# EEZ_DIB_AUX_PS_r1B1.net
KiCad netlist of a schematic drawn in EAGLE
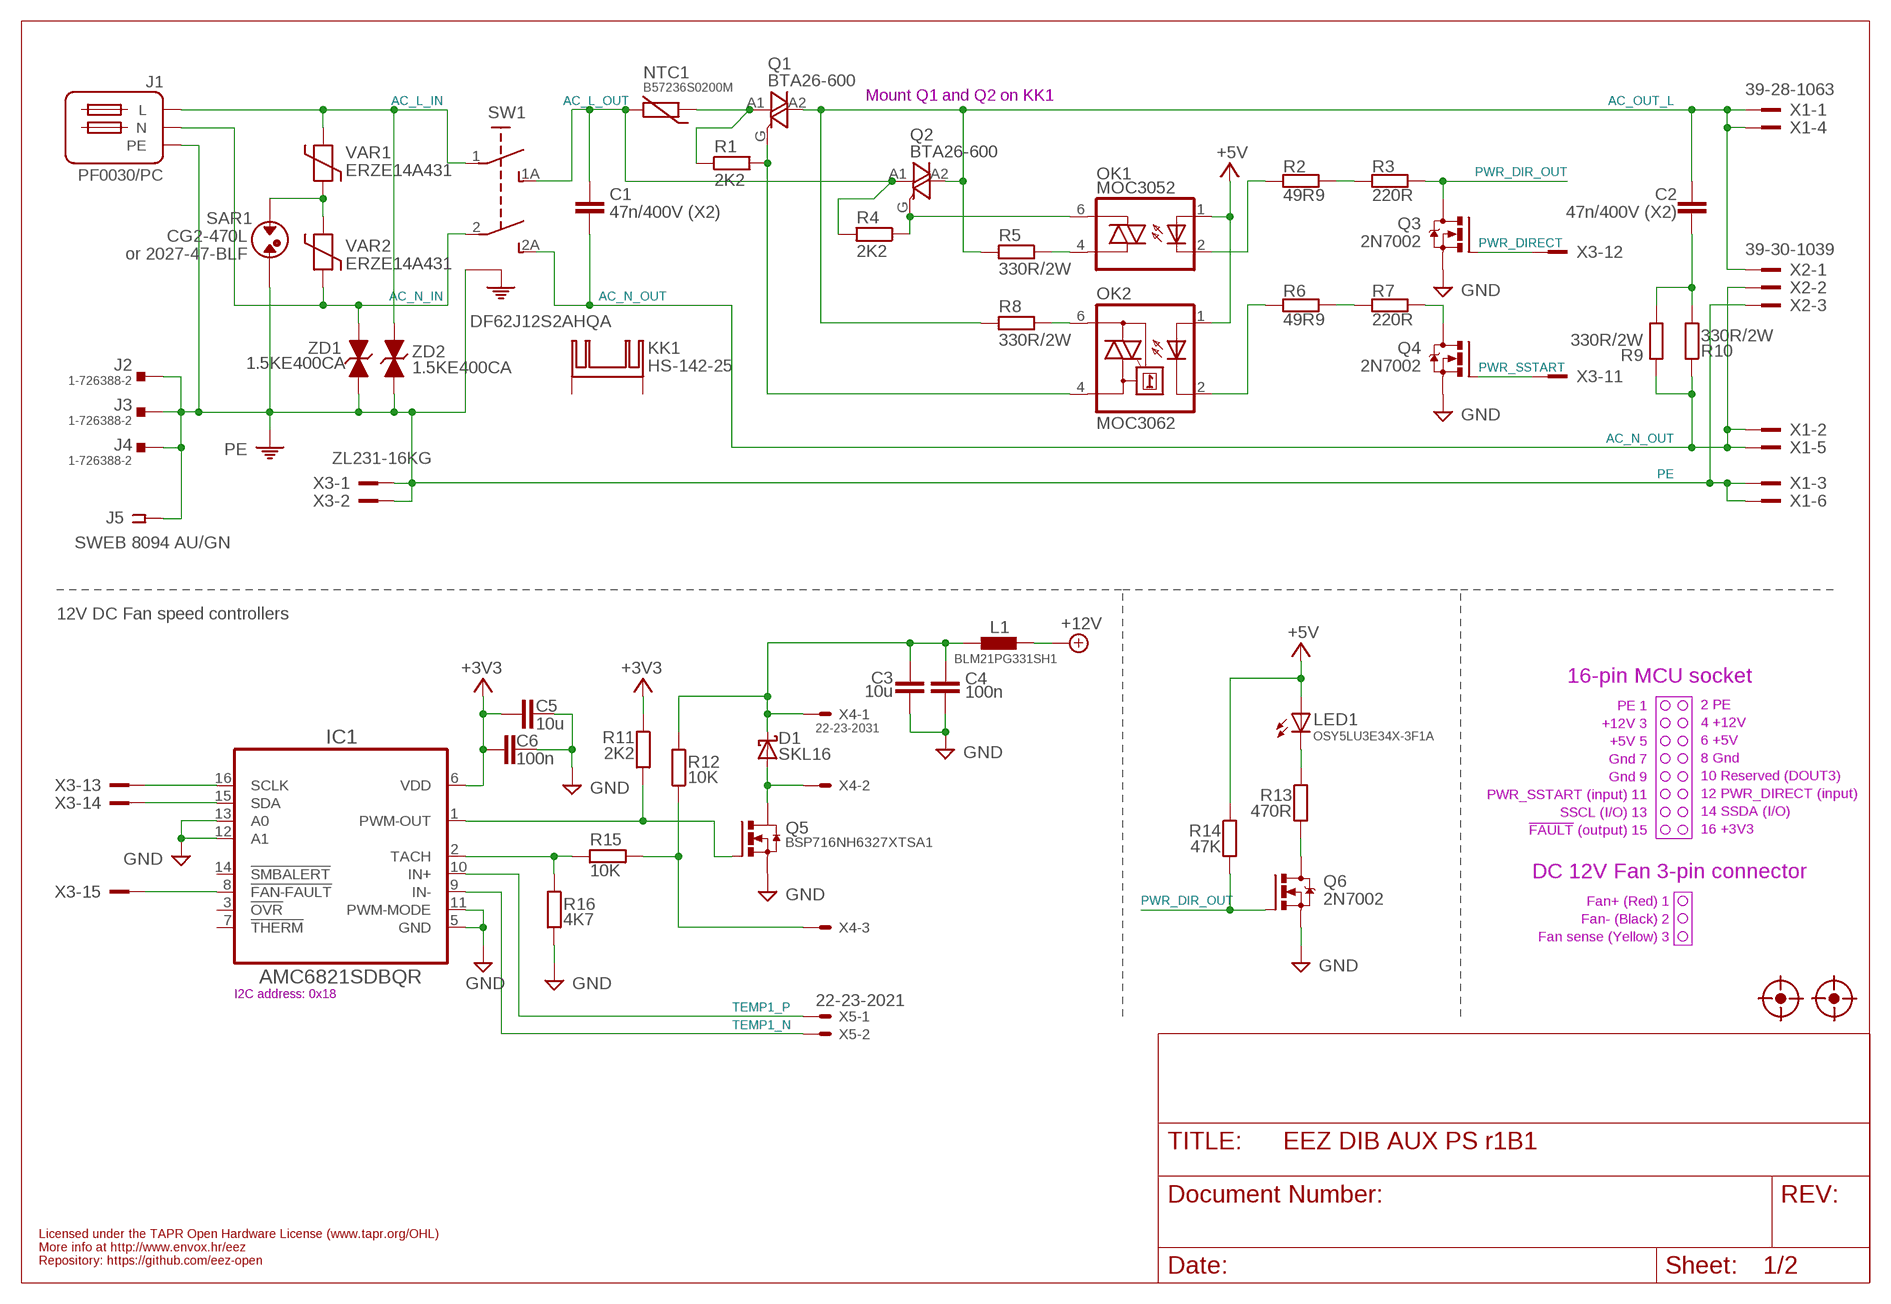
[diagram p0: schematic, sheet 1]
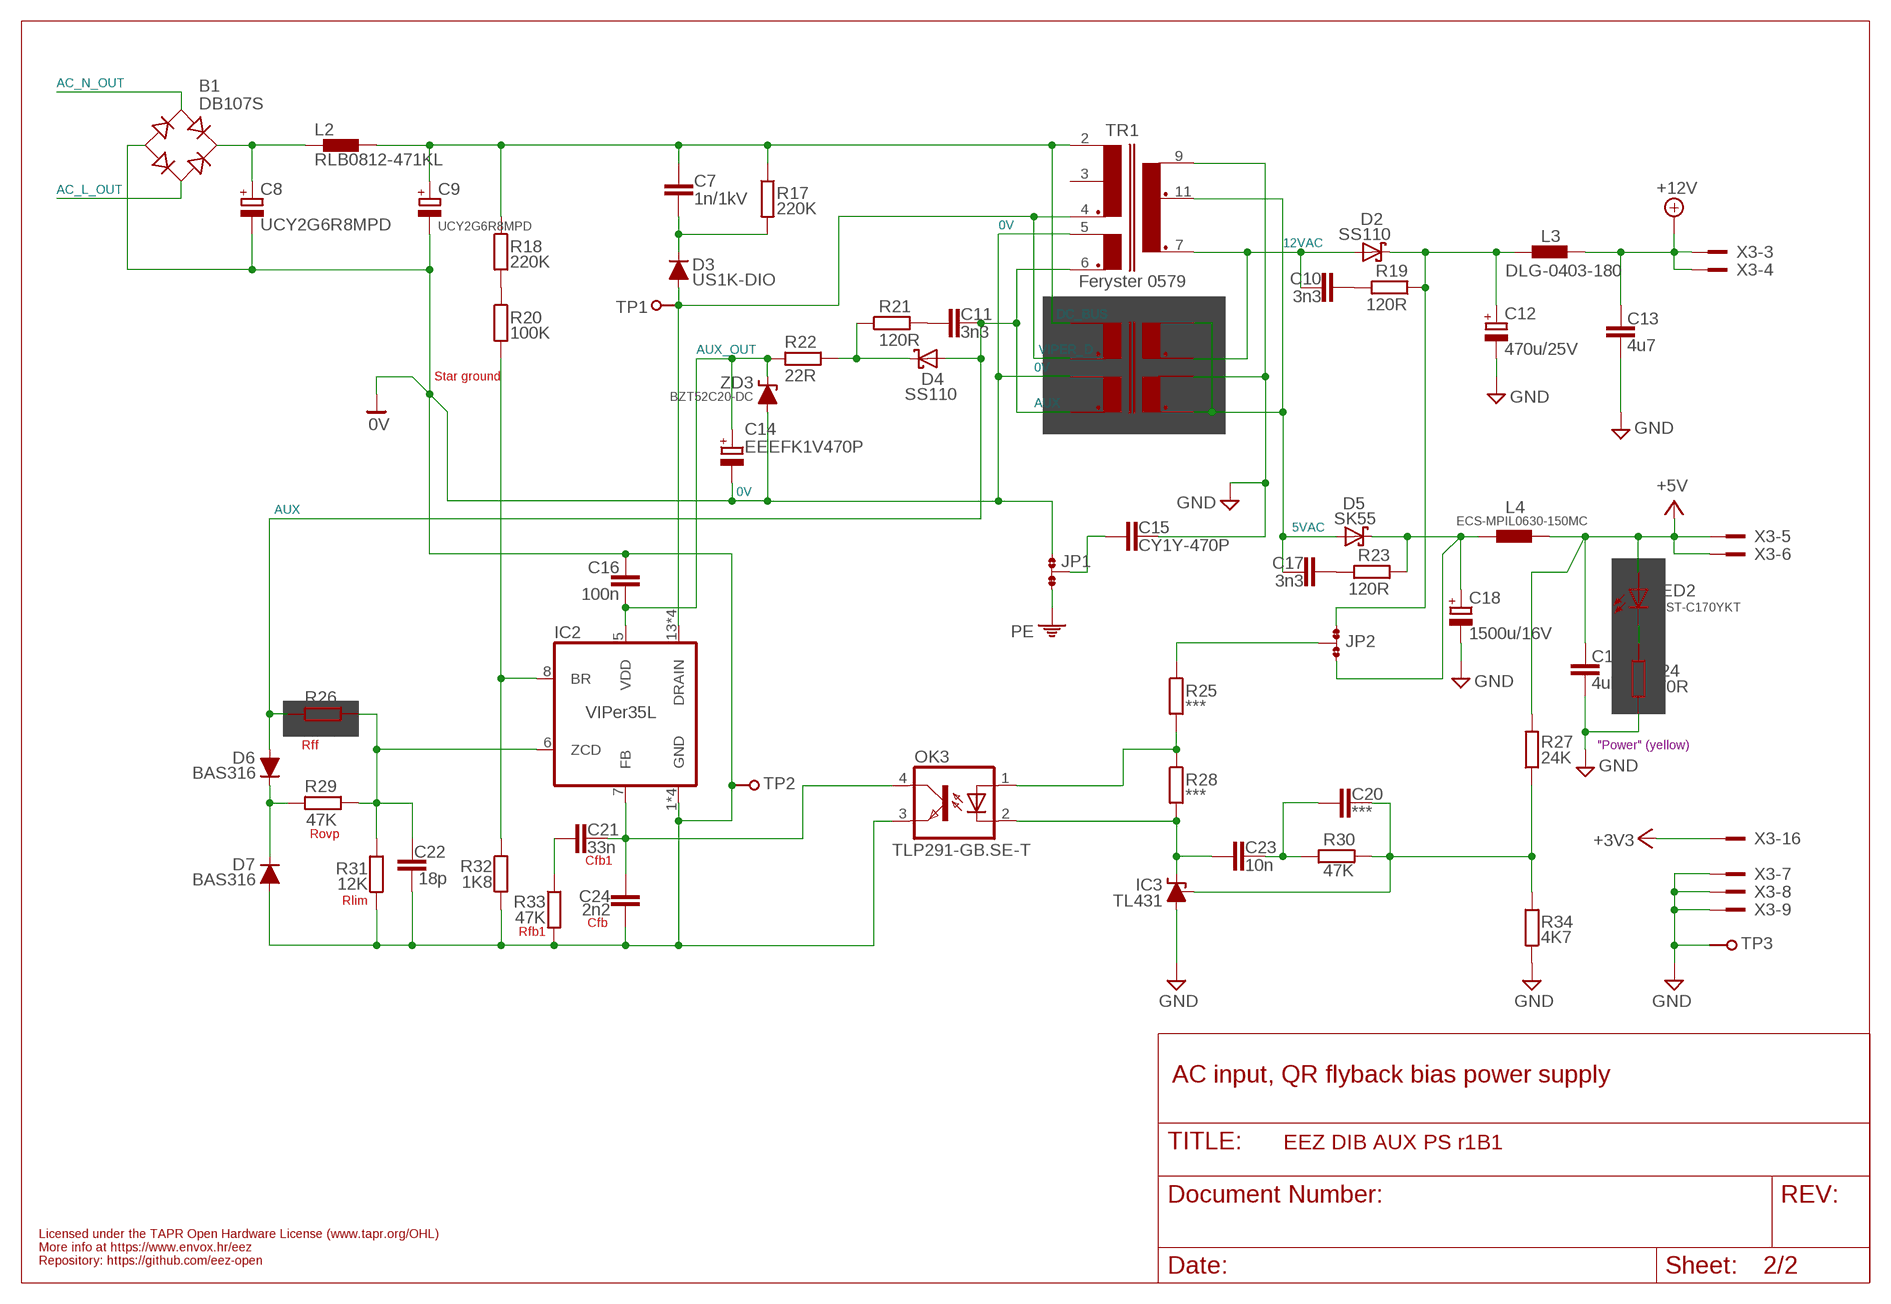
[diagram p1: schematic, sheet 2]

(export (version "E")
  (design (tool "Eeschema 10.0.6"))
  (components
    (comp (ref "C1")
      (value "47n/400V (X2)")
      (footprint "eagle-import:C102-054X133")
      (libsource (lib "eagle-import") (part "C-EU102-054X133"))
    )
    (comp (ref "C2")
      (value "47n/400V (X2)")
      (footprint "eagle-import:C102-054X133")
      (libsource (lib "eagle-import") (part "C-EU102-054X133"))
    )
    (comp (ref "C3")
      (value "10u")
      (footprint "eagle-import:C1206")
      (libsource (lib "eagle-import") (part "C-EUC1206"))
    )
    (comp (ref "C4")
      (value "100n")
      (footprint "eagle-import:C0603")
      (libsource (lib "eagle-import") (part "C-EUC0603"))
    )
    (comp (ref "C5")
      (value "10u")
      (footprint "eagle-import:C1206")
      (libsource (lib "eagle-import") (part "C-EUC1206"))
    )
    (comp (ref "C6")
      (value "100n")
      (footprint "eagle-import:C0603")
      (libsource (lib "eagle-import") (part "C-EUC0603"))
    )
    (comp (ref "D1")
      (value "SKL16")
      (footprint "eagle-import:SOD123")
      (libsource (lib "eagle-import") (part "SCHOTTKYSOD123"))
    )
    (comp (ref "FM1")
      (value "FIDUCIAL")
      (footprint "eagle-import:FIDUCIAL")
      (libsource (lib "eagle-import") (part "FIDUCIAL"))
    )
    (comp (ref "FM2")
      (value "FIDUCIAL")
      (footprint "eagle-import:FIDUCIAL")
      (libsource (lib "eagle-import") (part "FIDUCIAL"))
    )
    (comp (ref "IC1")
      (value "AMC6821SDBQR")
      (footprint "eagle-import:DBQ16")
      (fields
        (field (name "GENERIC_PART_NUMBER") "AMC6821")
        (field (name "MANUFACTURER") "Texas Instruments")
      )
      (libsource (lib "eagle-import") (part "AMC6821"))
    )
    (comp (ref "J1")
      (value "PF0030/PC")
      (footprint "eagle-import:PF0030_PC")
      (libsource (lib "eagle-import") (part "PF0030/PC"))
    )
    (comp (ref "J2")
      (value "1-726388-2")
      (footprint "eagle-import:PCB_TAB-4.8MM")
      (libsource (lib "eagle-import") (part "PCB_TAB4.8MM"))
    )
    (comp (ref "J3")
      (value "1-726388-2")
      (footprint "eagle-import:PCB_TAB-4.8MM")
      (libsource (lib "eagle-import") (part "PCB_TAB4.8MM"))
    )
    (comp (ref "J4")
      (value "1-726388-2")
      (footprint "eagle-import:PCB_TAB-4.8MM")
      (libsource (lib "eagle-import") (part "PCB_TAB4.8MM"))
    )
    (comp (ref "J5")
      (value "SWEB 8094 AU/GN")
      (footprint "eagle-import:S16N-PC")
      (libsource (lib "eagle-import") (part "BINDING_POSTCLIFF"))
    )
    (comp (ref "KK1")
      (value "HS-142-25")
      (footprint "eagle-import:SK129")
      (libsource (lib "eagle-import") (part "SK129-PAD"))
    )
    (comp (ref "L1")
      (value "BLM21PG331SH1")
      (footprint "eagle-import:0805")
      (libsource (lib "eagle-import") (part "L-EU0805"))
    )
    (comp (ref "LED1")
      (value "OSY5LU3E34X-3F1A")
      (footprint "eagle-import:OSG8")
      (libsource (lib "eagle-import") (part "LEDOSG8"))
    )
    (comp (ref "NTC1")
      (value "B57236S0200M")
      (footprint "eagle-import:NTC_11.5X6_RM5")
      (libsource (lib "eagle-import") (part "NTC11.5X6"))
    )
    (comp (ref "OK1")
      (value "MOC3052")
      (footprint "eagle-import:DIL6-SMD")
      (libsource (lib "eagle-import") (part "MOC305X"))
    )
    (comp (ref "OK2")
      (value "MOC3062")
      (footprint "eagle-import:DIL6-SMD")
      (fields
        (field (name "MF") "FAIRCHILD SEMICONDUCTOR")
        (field (name "MPN") "MOC3033S-M")
        (field (name "MF_1") "FAIRCHILD SEMICONDUCTOR")
        (field (name "MPN_1") "MOC3033S-M")
        (field (name "OC_FARNELL") "unknown")
        (field (name "OC_NEWARK") "05C2878")
      )
      (libsource (lib "eagle-import") (part "MOC30S33"))
    )
    (comp (ref "Q1")
      (value "BTA26-600")
      (footprint "eagle-import:TOP3S-1")
      (libsource (lib "eagle-import") (part "BTA26-V"))
    )
    (comp (ref "Q2")
      (value "BTA26-600")
      (footprint "eagle-import:TOP3S-1")
      (libsource (lib "eagle-import") (part "BTA26-V"))
    )
    (comp (ref "Q3")
      (value "2N7002")
      (footprint "eagle-import:SOT103P240X110-3N")
      (fields (field (name "MPN") "2N7002-7-F"))
      (libsource (lib "eagle-import") (part "2N7002"))
    )
    (comp (ref "Q4")
      (value "2N7002")
      (footprint "eagle-import:SOT103P240X110-3N")
      (fields (field (name "MPN") "2N7002-7-F"))
      (libsource (lib "eagle-import") (part "2N7002"))
    )
    (comp (ref "Q5")
      (value "BSP716NH6327XTSA1")
      (footprint "eagle-import:SOT223")
      (libsource (lib "eagle-import") (part "N-HEXFET-2D_?-SOT232IRLL014N"))
    )
    (comp (ref "Q6")
      (value "2N7002")
      (footprint "eagle-import:SOT103P240X110-3N")
      (fields
        (field (name "MPN") "2N7002-7-F")
        (field (name "MPN_1") "2N7002-7-F")
        (field (name "OC_FARNELL") "1713823")
        (field (name "OC_NEWARK") "25R5679")
        (field (name "PACKAGE") "SOT-23-3")
        (field (name "SUPPLIER") "DIODES INC.")
      )
      (libsource (lib "eagle-import") (part "2N7002"))
    )
    (comp (ref "R1")
      (value "2K2")
      (footprint "eagle-import:R0805")
      (libsource (lib "eagle-import") (part "R-EU_R0805"))
    )
    (comp (ref "R2")
      (value "49R9")
      (footprint "eagle-import:R0805")
      (libsource (lib "eagle-import") (part "R-EU_R0805"))
    )
    (comp (ref "R3")
      (value "220R")
      (footprint "eagle-import:R0805")
      (libsource (lib "eagle-import") (part "R-EU_R0805"))
    )
    (comp (ref "R4")
      (value "2K2")
      (footprint "eagle-import:R0805")
      (libsource (lib "eagle-import") (part "R-EU_R0805"))
    )
    (comp (ref "R5")
      (value "330R/2W")
      (footprint "eagle-import:R2512")
      (libsource (lib "eagle-import") (part "R-EU_R2512"))
    )
    (comp (ref "R6")
      (value "49R9")
      (footprint "eagle-import:R0805")
      (libsource (lib "eagle-import") (part "R-EU_R0805"))
    )
    (comp (ref "R7")
      (value "220R")
      (footprint "eagle-import:R0805")
      (libsource (lib "eagle-import") (part "R-EU_R0805"))
    )
    (comp (ref "R8")
      (value "330R/2W")
      (footprint "eagle-import:R2512")
      (libsource (lib "eagle-import") (part "R-EU_R2512"))
    )
    (comp (ref "R9")
      (value "330R/2W")
      (footprint "eagle-import:R2512")
      (libsource (lib "eagle-import") (part "R-EU_R2512"))
    )
    (comp (ref "R10")
      (value "330R/2W")
      (footprint "eagle-import:R2512")
      (libsource (lib "eagle-import") (part "R-EU_R2512"))
    )
    (comp (ref "R11")
      (value "2K2")
      (footprint "eagle-import:R0805")
      (libsource (lib "eagle-import") (part "R-EU_R0805"))
    )
    (comp (ref "R12")
      (value "10K")
      (footprint "eagle-import:R0805")
      (libsource (lib "eagle-import") (part "R-EU_R0805"))
    )
    (comp (ref "R13")
      (value "470R")
      (footprint "eagle-import:R0805")
      (libsource (lib "eagle-import") (part "R-EU_R0805"))
    )
    (comp (ref "R14")
      (value "47K")
      (footprint "eagle-import:R0805")
      (libsource (lib "eagle-import") (part "R-EU_R0805"))
    )
    (comp (ref "R15")
      (value "10K")
      (footprint "eagle-import:R0805")
      (libsource (lib "eagle-import") (part "R-EU_R0805"))
    )
    (comp (ref "R16")
      (value "4K7")
      (footprint "eagle-import:R0805")
      (libsource (lib "eagle-import") (part "R-EU_R0805"))
    )
    (comp (ref "SAR1")
      (value "CG2-470L")
      (footprint "eagle-import:SAR")
      (libsource (lib "eagle-import") (part "SAR"))
    )
    (comp (ref "SW1")
      (value "DF62J12S2AHQA")
      (footprint "eagle-import:DF62J12S2")
      (libsource (lib "eagle-import") (part "DF62J12S2AHQA"))
    )
    (comp (ref "VAR1")
      (value "ERZE14A431")
      (footprint "eagle-import:VARISTOR_13MM")
      (libsource (lib "eagle-import") (part "VARISTOR-13"))
    )
    (comp (ref "VAR2")
      (value "ERZE14A431")
      (footprint "eagle-import:VARISTOR_13MM")
      (libsource (lib "eagle-import") (part "VARISTOR-13"))
    )
    (comp (ref "X1")
      (value "39-28-1063")
      (footprint "eagle-import:MINIFIT_5566-06A_CRE")
      (libsource (lib "eagle-import") (part "MINIFIT_5566-06A-CRE"))
    )
    (comp (ref "X2")
      (value "39-30-1039")
      (footprint "eagle-import:MINIFIT_39301039_CRE")
      (libsource (lib "eagle-import") (part "MINIFIT_39301039-CREEPAGE"))
    )
    (comp (ref "X3")
      (value "ZL231-16KG")
      (footprint "eagle-import:ML16L")
      (libsource (lib "eagle-import") (part "IDC-16PIN-ANGLED"))
    )
    (comp (ref "X4")
      (value "22-23-2031")
      (footprint "eagle-import:22-23-2031")
      (fields (field (name "MF") "MOLEX"))
      (libsource (lib "eagle-import") (part "22-23-2031"))
    )
    (comp (ref "X5")
      (value "22-23-2021")
      (footprint "eagle-import:22-23-2021")
      (fields (field (name "MF") "MOLEX"))
      (libsource (lib "eagle-import") (part "22-23-2021"))
    )
    (comp (ref "ZD1")
      (value "1.5KE400CA")
      (footprint "eagle-import:DO201-BIDIR")
      (libsource (lib "eagle-import") (part "1.5KE-BIDIR"))
    )
    (comp (ref "ZD2")
      (value "1.5KE400CA")
      (footprint "eagle-import:DO201-BIDIR")
      (libsource (lib "eagle-import") (part "1.5KE-BIDIR"))
    )
    (comp (ref "B1")
      (value "DB107S")
      (footprint "eagle-import:DBS")
      (libsource (lib "eagle-import") (part "DB?GS107"))
    )
    (comp (ref "C7")
      (value "1n/1kV")
      (footprint "eagle-import:C1210")
      (libsource (lib "eagle-import") (part "C-EUC1210"))
    )
    (comp (ref "C8")
      (value "UCY2G6R8MPD")
      (footprint "eagle-import:ECAP5_10.5")
      (libsource (lib "eagle-import") (part "ECAP5G_10.5MM"))
    )
    (comp (ref "C9")
      (value "UCY2G6R8MPD")
      (footprint "eagle-import:ECAP5_10.5")
      (libsource (lib "eagle-import") (part "ECAP5G_10.5MM"))
    )
    (comp (ref "C10")
      (value "3n3")
      (footprint "eagle-import:C0805")
      (libsource (lib "eagle-import") (part "C-EUC0805"))
    )
    (comp (ref "C11")
      (value "3n3")
      (footprint "eagle-import:C0805")
      (libsource (lib "eagle-import") (part "C-EUC0805"))
    )
    (comp (ref "C12")
      (value "470u/25V")
      (footprint "eagle-import:ECAP5_10.5")
      (libsource (lib "eagle-import") (part "ECAP5G_10.5MM"))
    )
    (comp (ref "C13")
      (value "4u7")
      (footprint "eagle-import:C1206")
      (libsource (lib "eagle-import") (part "C-EUC1206"))
    )
    (comp (ref "C14")
      (value "EEEFK1V470P")
      (footprint "eagle-import:CAPAE660X610N")
      (libsource (lib "eagle-import") (part "ECAPPANASONIC_H"))
    )
    (comp (ref "C15")
      (value "CY1Y-470P")
      (footprint "eagle-import:CY075-032X103")
      (libsource (lib "eagle-import") (part "C-EUCY"))
    )
    (comp (ref "C16")
      (value "100n")
      (footprint "eagle-import:C0603")
      (libsource (lib "eagle-import") (part "C-EUC0603"))
    )
    (comp (ref "C17")
      (value "3n3")
      (footprint "eagle-import:C0805")
      (libsource (lib "eagle-import") (part "C-EUC0805"))
    )
    (comp (ref "C18")
      (value "1500u/16V")
      (footprint "eagle-import:ECAP5_13")
      (libsource (lib "eagle-import") (part "ECAP5G_13MM"))
    )
    (comp (ref "C19")
      (value "4u7")
      (footprint "eagle-import:C1206")
      (libsource (lib "eagle-import") (part "C-EUC1206"))
    )
    (comp (ref "C20")
      (value "***")
      (footprint "eagle-import:C0805")
      (libsource (lib "eagle-import") (part "C-EUC0805"))
    )
    (comp (ref "C21")
      (value "33n")
      (footprint "eagle-import:C0805")
      (libsource (lib "eagle-import") (part "C-EUC0805"))
    )
    (comp (ref "C22")
      (value "18p")
      (footprint "eagle-import:C0603")
      (libsource (lib "eagle-import") (part "C-EUC0603"))
    )
    (comp (ref "C23")
      (value "10n")
      (footprint "eagle-import:C0805")
      (libsource (lib "eagle-import") (part "C-EUC0805"))
    )
    (comp (ref "C24")
      (value "2n2")
      (footprint "eagle-import:C0805")
      (libsource (lib "eagle-import") (part "C-EUC0805"))
    )
    (comp (ref "D2")
      (value "SS110")
      (footprint "eagle-import:SMB")
      (libsource (lib "eagle-import") (part "SCHOTTKYSMB"))
    )
    (comp (ref "D3")
      (value "US1K-DIO")
      (footprint "eagle-import:DO214AA")
      (libsource (lib "eagle-import") (part "DIODEDO214AA"))
    )
    (comp (ref "D4")
      (value "SS110")
      (footprint "eagle-import:SMB")
      (libsource (lib "eagle-import") (part "SCHOTTKYSMB"))
    )
    (comp (ref "D5")
      (value "SK55")
      (footprint "eagle-import:SMB")
      (libsource (lib "eagle-import") (part "SCHOTTKYSMB"))
    )
    (comp (ref "D6")
      (value "BAS316")
      (footprint "eagle-import:SOD323-R")
      (libsource (lib "eagle-import") (part "DIODESOD323R"))
    )
    (comp (ref "D7")
      (value "BAS316")
      (footprint "eagle-import:SOD323-R")
      (libsource (lib "eagle-import") (part "DIODESOD323R"))
    )
    (comp (ref "IC2")
      (value "VIPer35L")
      (footprint "eagle-import:SOIC-16")
      (libsource (lib "eagle-import") (part "VIPER35"))
    )
    (comp (ref "IC3")
      (value "TL431")
      (footprint "eagle-import:SOT103P240X110-3N")
      (libsource (lib "eagle-import") (part "TL431"))
    )
    (comp (ref "JP1")
      (value "JP3-CUT")
      (footprint "eagle-import:JP3-CUT")
      (libsource (lib "eagle-import") (part "JP3-CUT"))
    )
    (comp (ref "JP2")
      (value "JP3-CUT")
      (footprint "eagle-import:JP3-CUT")
      (libsource (lib "eagle-import") (part "JP3-CUT"))
    )
    (comp (ref "L2")
      (value "RLB0812-471KL")
      (footprint "eagle-import:FERSYTER_DSZ6")
      (libsource (lib "eagle-import") (part "FERYSTER_DSZ6"))
    )
    (comp (ref "L3")
      (value "DLG-0403-180")
      (footprint "eagle-import:DE0403")
      (libsource (lib "eagle-import") (part "EEZ_inductors_and_transformers_DE0403"))
    )
    (comp (ref "L4")
      (value "ECS-MPIL0630-150MC")
      (footprint "eagle-import:DE0704")
      (libsource (lib "eagle-import") (part "DE0704"))
    )
    (comp (ref "LED2")
      (value "LTST-C170YKT")
      (footprint "eagle-import:LED_0805")
      (libsource (lib "eagle-import") (part "LED0805"))
    )
    (comp (ref "OK3")
      (value "TLP291-GB.SE-T")
      (footprint "eagle-import:SO4")
      (libsource (lib "eagle-import") (part "TLP291"))
    )
    (comp (ref "R17")
      (value "220K")
      (footprint "eagle-import:R1206")
      (libsource (lib "eagle-import") (part "R-EU_R1206"))
    )
    (comp (ref "R18")
      (value "220K")
      (footprint "eagle-import:R1206")
      (libsource (lib "eagle-import") (part "R-EU_R1206"))
    )
    (comp (ref "R19")
      (value "120R")
      (footprint "eagle-import:R0805")
      (libsource (lib "eagle-import") (part "R-EU_R0805"))
    )
    (comp (ref "R20")
      (value "100K")
      (footprint "eagle-import:R0805")
      (libsource (lib "eagle-import") (part "R-EU_R0805"))
    )
    (comp (ref "R21")
      (value "120R")
      (footprint "eagle-import:R0805")
      (libsource (lib "eagle-import") (part "R-EU_R0805"))
    )
    (comp (ref "R22")
      (value "22R")
      (footprint "eagle-import:R0805")
      (libsource (lib "eagle-import") (part "R-EU_R0805"))
    )
    (comp (ref "R23")
      (value "120R")
      (footprint "eagle-import:R0805")
      (libsource (lib "eagle-import") (part "R-EU_R0805"))
    )
    (comp (ref "R24")
      (value "470R")
      (footprint "eagle-import:R0805")
      (libsource (lib "eagle-import") (part "R-EU_R0805"))
    )
    (comp (ref "R25")
      (value "***")
      (footprint "eagle-import:R0805")
      (libsource (lib "eagle-import") (part "R-EU_R0805"))
    )
    (comp (ref "R26")
      (value "N.C.")
      (footprint "eagle-import:R0805")
      (libsource (lib "eagle-import") (part "R-EU_R0805"))
    )
    (comp (ref "R27")
      (value "24K")
      (footprint "eagle-import:R0805")
      (libsource (lib "eagle-import") (part "R-EU_R0805"))
    )
    (comp (ref "R28")
      (value "***")
      (footprint "eagle-import:R0805")
      (libsource (lib "eagle-import") (part "R-EU_R0805"))
    )
    (comp (ref "R29")
      (value "47K")
      (footprint "eagle-import:R0805")
      (libsource (lib "eagle-import") (part "R-EU_R0805"))
    )
    (comp (ref "R30")
      (value "47K")
      (footprint "eagle-import:R0805")
      (libsource (lib "eagle-import") (part "R-EU_R0805"))
    )
    (comp (ref "R31")
      (value "12K")
      (footprint "eagle-import:R0805")
      (libsource (lib "eagle-import") (part "R-EU_R0805"))
    )
    (comp (ref "R32")
      (value "1K8")
      (footprint "eagle-import:R0805")
      (libsource (lib "eagle-import") (part "R-EU_R0805"))
    )
    (comp (ref "R33")
      (value "47K")
      (footprint "eagle-import:R0805")
      (libsource (lib "eagle-import") (part "R-EU_R0805"))
    )
    (comp (ref "R34")
      (value "4K7")
      (footprint "eagle-import:R0805")
      (libsource (lib "eagle-import") (part "R-EU_R0805"))
    )
    (comp (ref "TP1")
      (value "PCB_TEST_TABSHIELD")
      (footprint "eagle-import:PCB_SHIELD_TAB")
      (libsource (lib "eagle-import") (part "PCB_TEST_TABSHIELD"))
    )
    (comp (ref "TP2")
      (value "PCB_TEST_TABSHIELD")
      (footprint "eagle-import:PCB_SHIELD_TAB")
      (libsource (lib "eagle-import") (part "PCB_TEST_TABSHIELD"))
    )
    (comp (ref "TP3")
      (value "PCB_TEST_TABSHIELD")
      (footprint "eagle-import:PCB_SHIELD_TAB")
      (libsource (lib "eagle-import") (part "PCB_TEST_TABSHIELD"))
    )
    (comp (ref "TR1")
      (value "Feryster 0579")
      (footprint "eagle-import:FERYSTER_0579")
      (libsource (lib "eagle-import") (part "FERYSTER_0579"))
    )
    (comp (ref "TR1B")
      (value "(WE 760875532)")
      (footprint "eagle-import:WE-UOST")
      (libsource (lib "eagle-import") (part "WE-UOST"))
    )
    (comp (ref "ZD3")
      (value "BZT52C20-DC")
      (footprint "eagle-import:SOD123")
      (libsource (lib "eagle-import") (part "ZENER-DIODESOD123"))
    )
  )
  (nets
    (net (code "1") (name "+3V3") (class "Default")
      (node (ref "C5") (pin "2") (pinfunction "2_2") (pintype "passive"))
      (node (ref "C6") (pin "2") (pinfunction "2_2") (pintype "passive"))
      (node (ref "IC1") (pin "6") (pinfunction "VDD_6") (pintype "power_in"))
      (node (ref "R11") (pin "1") (pinfunction "1_1") (pintype "passive"))
      (node (ref "X3") (pin "16") (pinfunction "1_16") (pintype "passive"))
    )
    (net (code "2") (name "+5V") (class "Default")
      (node (ref "C19") (pin "1") (pinfunction "1_1") (pintype "passive"))
      (node (ref "L4") (pin "2") (pinfunction "2_2") (pintype "passive"))
      (node (ref "LED1") (pin "A") (pinfunction "A_A") (pintype "passive"))
      (node (ref "LED2") (pin "A") (pinfunction "A_A") (pintype "passive"))
      (node (ref "OK1") (pin "1") (pinfunction "A_1") (pintype "passive"))
      (node (ref "OK2") (pin "1") (pinfunction "A_1") (pintype "passive"))
      (node (ref "R14") (pin "1") (pinfunction "1_1") (pintype "passive"))
      (node (ref "R27") (pin "2") (pinfunction "2_2") (pintype "passive"))
      (node (ref "X3") (pin "5") (pinfunction "1_5") (pintype "passive"))
      (node (ref "X3") (pin "6") (pinfunction "1_6") (pintype "passive"))
    )
    (net (code "3") (name "+12V") (class "Default")
      (node (ref "C13") (pin "1") (pinfunction "1_1") (pintype "passive"))
      (node (ref "L1") (pin "2") (pinfunction "2_2") (pintype "passive"))
      (node (ref "L3") (pin "2") (pinfunction "2_2") (pintype "passive"))
      (node (ref "X3") (pin "3") (pinfunction "1_3") (pintype "passive"))
      (node (ref "X3") (pin "4") (pinfunction "1_4") (pintype "passive"))
    )
    (net (code "4") (name "0V") (class "Default")
      (node (ref "B1") (pin "-") (pinfunction "-_-") (pintype "passive"))
      (node (ref "C14") (pin "2") (pinfunction "-_2") (pintype "passive"))
      (node (ref "C16") (pin "1") (pinfunction "1_1") (pintype "passive"))
      (node (ref "C22") (pin "2") (pinfunction "2_2") (pintype "passive"))
      (node (ref "C24") (pin "2") (pinfunction "2_2") (pintype "passive"))
      (node (ref "C8") (pin "-") (pinfunction "-_-") (pintype "passive"))
      (node (ref "C9") (pin "-") (pinfunction "-_-") (pintype "passive"))
      (node (ref "D7") (pin "A") (pinfunction "A_A") (pintype "passive"))
      (node (ref "IC2") (pin "1") (pinfunction "GND_1") (pintype "passive"))
      (node (ref "IC2") (pin "2") (pinfunction "GND_2") (pintype "passive"))
      (node (ref "IC2") (pin "3") (pinfunction "GND_3") (pintype "passive"))
      (node (ref "IC2") (pin "4") (pinfunction "GND_4") (pintype "passive"))
      (node (ref "JP1") (pin "NO") (pinfunction "NO_NO") (pintype "passive"))
      (node (ref "OK3") (pin "3") (pinfunction "EMIT_3") (pintype "passive"))
      (node (ref "R31") (pin "1") (pinfunction "1_1") (pintype "passive"))
      (node (ref "R32") (pin "2") (pinfunction "2_2") (pintype "passive"))
      (node (ref "R33") (pin "2") (pinfunction "2_2") (pintype "passive"))
      (node (ref "TP2") (pin "1") (pinfunction "P$1_1") (pintype "bidirectional"))
      (node (ref "TR1") (pin "5") (pinfunction "AUX_5") (pintype "passive"))
      (node (ref "TR1B") (pin "11") (pinfunction "AUX_11") (pintype "passive"))
      (node (ref "ZD3") (pin "A") (pinfunction "A_A") (pintype "passive"))
    )
    (net (code "5") (name "5VAC") (class "Default")
      (node (ref "C17") (pin "2") (pinfunction "2_2") (pintype "passive"))
      (node (ref "D5") (pin "A") (pinfunction "A_A") (pintype "passive"))
      (node (ref "TR1") (pin "11") (pinfunction "S1_DOT_11") (pintype "passive"))
      (node (ref "TR1B") (pin "2") (pinfunction "S1_2") (pintype "passive"))
      (node (ref "TR1B") (pin "3") (pinfunction "S2_DOT_3") (pintype "passive"))
      (node (ref "TR1B") (pin "4") (pinfunction "S2_DOT_4") (pintype "passive"))
    )
    (net (code "6") (name "12VAC") (class "Default")
      (node (ref "C10") (pin "2") (pinfunction "2_2") (pintype "passive"))
      (node (ref "D2") (pin "A") (pinfunction "A_A") (pintype "passive"))
      (node (ref "TR1") (pin "7") (pinfunction "S2_DOT_7") (pintype "passive"))
      (node (ref "TR1B") (pin "1") (pinfunction "S1_DOT_1") (pintype "passive"))
    )
    (net (code "7") (name "AC_L_IN") (class "Default")
      (node (ref "J1") (pin "L") (pinfunction "L_L") (pintype "bidirectional"))
      (node (ref "SW1") (pin "1") (pinfunction "P_1") (pintype "passive"))
      (node (ref "VAR1") (pin "2") (pinfunction "P$2_2") (pintype "bidirectional"))
      (node (ref "ZD2") (pin "A") (pinfunction "2_A") (pintype "passive"))
    )
    (net (code "8") (name "AC_L_OUT") (class "Default")
      (node (ref "B1") (pin "AC2") (pinfunction "AC2_AC2") (pintype "passive"))
      (node (ref "C1") (pin "1") (pinfunction "1_1") (pintype "passive"))
      (node (ref "NTC1") (pin "1") (pinfunction "P$1_1") (pintype "bidirectional"))
      (node (ref "Q2") (pin "A1") (pinfunction "A1_A1") (pintype "passive"))
      (node (ref "R4") (pin "2") (pinfunction "2_2") (pintype "passive"))
      (node (ref "SW1") (pin "1A") (pinfunction "S_1A") (pintype "passive"))
    )
    (net (code "9") (name "AC_N_IN") (class "Default")
      (node (ref "J1") (pin "N") (pinfunction "N_N") (pintype "bidirectional"))
      (node (ref "SW1") (pin "2") (pinfunction "P1_2") (pintype "passive"))
      (node (ref "VAR2") (pin "1") (pinfunction "P$1_1") (pintype "bidirectional"))
      (node (ref "ZD1") (pin "A") (pinfunction "2_A") (pintype "passive"))
    )
    (net (code "10") (name "AC_N_OUT") (class "Default")
      (node (ref "B1") (pin "AC1") (pinfunction "AC1_AC1") (pintype "passive"))
      (node (ref "C1") (pin "2") (pinfunction "2_2") (pintype "passive"))
      (node (ref "R10") (pin "1") (pinfunction "1_1") (pintype "passive"))
      (node (ref "R9") (pin "1") (pinfunction "1_1") (pintype "passive"))
      (node (ref "SW1") (pin "2A") (pinfunction "S1_2A") (pintype "passive"))
      (node (ref "X1") (pin "2") (pinfunction "1_2") (pintype "passive"))
      (node (ref "X1") (pin "5") (pinfunction "1_5") (pintype "passive"))
      (node (ref "X2") (pin "2") (pinfunction "1_2") (pintype "passive"))
    )
    (net (code "11") (name "AC_OUT_L") (class "Default")
      (node (ref "C2") (pin "1") (pinfunction "1_1") (pintype "passive"))
      (node (ref "Q1") (pin "A2") (pinfunction "A2_A2") (pintype "passive"))
      (node (ref "Q2") (pin "A2") (pinfunction "A2_A2") (pintype "passive"))
      (node (ref "R5") (pin "2") (pinfunction "2_2") (pintype "passive"))
      (node (ref "R8") (pin "2") (pinfunction "2_2") (pintype "passive"))
      (node (ref "X1") (pin "1") (pinfunction "1_1") (pintype "passive"))
      (node (ref "X1") (pin "4") (pinfunction "1_4") (pintype "passive"))
      (node (ref "X2") (pin "1") (pinfunction "1_1") (pintype "passive"))
    )
    (net (code "12") (name "AUX") (class "Default")
      (node (ref "C11") (pin "2") (pinfunction "2_2") (pintype "passive"))
      (node (ref "D4") (pin "A") (pinfunction "A_A") (pintype "passive"))
      (node (ref "D6") (pin "A") (pinfunction "A_A") (pintype "passive"))
      (node (ref "R26") (pin "2") (pinfunction "2_2") (pintype "passive"))
      (node (ref "TR1") (pin "6") (pinfunction "AUX_DOT_6") (pintype "passive"))
      (node (ref "TR1B") (pin "12") (pinfunction "AUX_DOT_12") (pintype "passive"))
    )
    (net (code "13") (name "AUX_OUT") (class "Default")
      (node (ref "C14") (pin "1") (pinfunction "+_1") (pintype "passive"))
      (node (ref "C16") (pin "2") (pinfunction "2_2") (pintype "passive"))
      (node (ref "IC2") (pin "5") (pinfunction "VDD_5") (pintype "power_in"))
      (node (ref "R22") (pin "2") (pinfunction "2_2") (pintype "passive"))
      (node (ref "ZD3") (pin "C") (pinfunction "C_C") (pintype "passive"))
    )
    (net (code "14") (name "DC_BUS") (class "Default")
      (node (ref "C7") (pin "1") (pinfunction "1_1") (pintype "passive"))
      (node (ref "C9") (pin "+") (pinfunction "+_+") (pintype "passive"))
      (node (ref "L2") (pin "P$2") (pinfunction "2_P$2") (pintype "passive"))
      (node (ref "R17") (pin "1") (pinfunction "1_1") (pintype "passive"))
      (node (ref "R18") (pin "1") (pinfunction "1_1") (pintype "passive"))
      (node (ref "TR1") (pin "2") (pinfunction "P1_2") (pintype "passive"))
      (node (ref "TR1B") (pin "7") (pinfunction "P1_7") (pintype "passive"))
    )
    (net (code "15") (name "GND") (class "Default")
      (node (ref "C12") (pin "-") (pinfunction "-_-") (pintype "passive"))
      (node (ref "C13") (pin "2") (pinfunction "2_2") (pintype "passive"))
      (node (ref "C15") (pin "2") (pinfunction "2_2") (pintype "passive"))
      (node (ref "C18") (pin "-") (pinfunction "-_-") (pintype "passive"))
      (node (ref "C19") (pin "2") (pinfunction "2_2") (pintype "passive"))
      (node (ref "C3") (pin "2") (pinfunction "2_2") (pintype "passive"))
      (node (ref "C4") (pin "2") (pinfunction "2_2") (pintype "passive"))
      (node (ref "C5") (pin "1") (pinfunction "1_1") (pintype "passive"))
      (node (ref "C6") (pin "1") (pinfunction "1_1") (pintype "passive"))
      (node (ref "IC1") (pin "11") (pinfunction "PWM-MODE_11") (pintype "input"))
      (node (ref "IC1") (pin "12") (pinfunction "A1_12") (pintype "passive"))
      (node (ref "IC1") (pin "13") (pinfunction "A0_13") (pintype "passive"))
      (node (ref "IC1") (pin "5") (pinfunction "GND_5") (pintype "power_in"))
      (node (ref "IC3") (pin "3") (pinfunction "A_3") (pintype "passive"))
      (node (ref "Q3") (pin "2") (pinfunction "S_2") (pintype "passive"))
      (node (ref "Q4") (pin "2") (pinfunction "S_2") (pintype "passive"))
      (node (ref "Q5") (pin "3") (pinfunction "S_3") (pintype "passive"))
      (node (ref "Q6") (pin "2") (pinfunction "S_2") (pintype "passive"))
      (node (ref "R16") (pin "2") (pinfunction "2_2") (pintype "passive"))
      (node (ref "R24") (pin "2") (pinfunction "2_2") (pintype "passive"))
      (node (ref "R34") (pin "1") (pinfunction "1_1") (pintype "passive"))
      (node (ref "TP3") (pin "1") (pinfunction "P$1_1") (pintype "bidirectional"))
      (node (ref "TR1") (pin "9") (pinfunction "S_COMM_9") (pintype "passive"))
      (node (ref "TR1B") (pin "5") (pinfunction "S2_5") (pintype "passive"))
      (node (ref "TR1B") (pin "6") (pinfunction "S2_6") (pintype "passive"))
      (node (ref "X3") (pin "7") (pinfunction "1_7") (pintype "passive"))
      (node (ref "X3") (pin "8") (pinfunction "1_8") (pintype "passive"))
      (node (ref "X3") (pin "9") (pinfunction "1_9") (pintype "passive"))
    )
    (net (code "16") (name "Net-(C2-Pad2)") (class "Default")
      (node (ref "C2") (pin "2") (pinfunction "2_2") (pintype "passive"))
      (node (ref "R10") (pin "2") (pinfunction "2_2") (pintype "passive"))
      (node (ref "R9") (pin "2") (pinfunction "2_2") (pintype "passive"))
    )
    (net (code "17") (name "Net-(C7-Pad2)") (class "Default")
      (node (ref "C7") (pin "2") (pinfunction "2_2") (pintype "passive"))
      (node (ref "D3") (pin "C") (pinfunction "C_C") (pintype "passive"))
      (node (ref "R17") (pin "2") (pinfunction "2_2") (pintype "passive"))
    )
    (net (code "18") (name "Net-(C10-Pad1)") (class "Default")
      (node (ref "C10") (pin "1") (pinfunction "1_1") (pintype "passive"))
      (node (ref "R19") (pin "2") (pinfunction "2_2") (pintype "passive"))
    )
    (net (code "19") (name "Net-(C11-Pad1)") (class "Default")
      (node (ref "C11") (pin "1") (pinfunction "1_1") (pintype "passive"))
      (node (ref "R21") (pin "2") (pinfunction "2_2") (pintype "passive"))
    )
    (net (code "20") (name "Net-(C12-Pad+)") (class "Default")
      (node (ref "C12") (pin "+") (pinfunction "+_+") (pintype "passive"))
      (node (ref "D2") (pin "C") (pinfunction "C_C") (pintype "passive"))
      (node (ref "JP2") (pin "NC") (pinfunction "NC_NC") (pintype "passive"))
      (node (ref "L3") (pin "1") (pinfunction "1_1") (pintype "passive"))
      (node (ref "R19") (pin "1") (pinfunction "1_1") (pintype "passive"))
    )
    (net (code "21") (name "Net-(C15-Pad1)") (class "Default")
      (node (ref "C15") (pin "1") (pinfunction "1_1") (pintype "passive"))
      (node (ref "JP1") (pin "COM") (pinfunction "COM_COM") (pintype "passive"))
    )
    (net (code "22") (name "Net-(C17-Pad1)") (class "Default")
      (node (ref "C17") (pin "1") (pinfunction "1_1") (pintype "passive"))
      (node (ref "R23") (pin "2") (pinfunction "2_2") (pintype "passive"))
    )
    (net (code "23") (name "Net-(C18-Pad+)") (class "Default")
      (node (ref "C18") (pin "+") (pinfunction "+_+") (pintype "passive"))
      (node (ref "D5") (pin "C") (pinfunction "C_C") (pintype "passive"))
      (node (ref "JP2") (pin "NO") (pinfunction "NO_NO") (pintype "passive"))
      (node (ref "L4") (pin "1") (pinfunction "1_1") (pintype "passive"))
      (node (ref "R23") (pin "1") (pinfunction "1_1") (pintype "passive"))
    )
    (net (code "24") (name "Net-(C20-Pad1)") (class "Default")
      (node (ref "C20") (pin "1") (pinfunction "1_1") (pintype "passive"))
      (node (ref "C23") (pin "2") (pinfunction "2_2") (pintype "passive"))
      (node (ref "R30") (pin "1") (pinfunction "1_1") (pintype "passive"))
    )
    (net (code "25") (name "Net-(C21-Pad1)") (class "Default")
      (node (ref "C21") (pin "1") (pinfunction "1_1") (pintype "passive"))
      (node (ref "R33") (pin "1") (pinfunction "1_1") (pintype "passive"))
    )
    (net (code "26") (name "Net-(D4-PadC)") (class "Default")
      (node (ref "D4") (pin "C") (pinfunction "C_C") (pintype "passive"))
      (node (ref "R21") (pin "1") (pinfunction "1_1") (pintype "passive"))
      (node (ref "R22") (pin "1") (pinfunction "1_1") (pintype "passive"))
    )
    (net (code "27") (name "Net-(D6-PadC)") (class "Default")
      (node (ref "D6") (pin "C") (pinfunction "C_C") (pintype "passive"))
      (node (ref "D7") (pin "C") (pinfunction "C_C") (pintype "passive"))
      (node (ref "R29") (pin "2") (pinfunction "2_2") (pintype "passive"))
    )
    (net (code "28") (name "Net-(IC1-PWM-OUT)") (class "Default")
      (node (ref "IC1") (pin "1") (pinfunction "PWM-OUT_1") (pintype "output"))
      (node (ref "Q5") (pin "1") (pinfunction "G_1") (pintype "passive"))
      (node (ref "R11") (pin "2") (pinfunction "2_2") (pintype "passive"))
    )
    (net (code "29") (name "Net-(IC1-SCLK)") (class "Default")
      (node (ref "IC1") (pin "16") (pinfunction "SCLK_16") (pintype "input"))
      (node (ref "X3") (pin "13") (pinfunction "1_13") (pintype "passive"))
    )
    (net (code "30") (name "Net-(IC1-SDA)") (class "Default")
      (node (ref "IC1") (pin "15") (pinfunction "SDA_15") (pintype "bidirectional"))
      (node (ref "X3") (pin "14") (pinfunction "1_14") (pintype "passive"))
    )
    (net (code "31") (name "Net-(IC1-TACH)") (class "Default")
      (node (ref "IC1") (pin "2") (pinfunction "TACH_2") (pintype "input"))
      (node (ref "R15") (pin "1") (pinfunction "1_1") (pintype "passive"))
      (node (ref "R16") (pin "1") (pinfunction "1_1") (pintype "passive"))
    )
    (net (code "32") (name "Net-(IC1-~{FAN-FAULT})") (class "Default")
      (node (ref "IC1") (pin "8") (pinfunction "~{FAN-FAULT}_8") (pintype "output"))
      (node (ref "X3") (pin "15") (pinfunction "1_15") (pintype "passive"))
    )
    (net (code "33") (name "Net-(IC2-BR)") (class "Default")
      (node (ref "IC2") (pin "8") (pinfunction "BR_8") (pintype "input"))
      (node (ref "R20") (pin "2") (pinfunction "2_2") (pintype "passive"))
      (node (ref "R32") (pin "1") (pinfunction "1_1") (pintype "passive"))
    )
    (net (code "34") (name "Net-(IC2-FB)") (class "Default")
      (node (ref "C21") (pin "2") (pinfunction "2_2") (pintype "passive"))
      (node (ref "C24") (pin "1") (pinfunction "1_1") (pintype "passive"))
      (node (ref "IC2") (pin "7") (pinfunction "FB_7") (pintype "input"))
      (node (ref "OK3") (pin "4") (pinfunction "COL_4") (pintype "passive"))
    )
    (net (code "35") (name "Net-(IC2-ZCD)") (class "Default")
      (node (ref "C22") (pin "1") (pinfunction "1_1") (pintype "passive"))
      (node (ref "IC2") (pin "6") (pinfunction "ZCD_6") (pintype "input"))
      (node (ref "R26") (pin "1") (pinfunction "1_1") (pintype "passive"))
      (node (ref "R29") (pin "1") (pinfunction "1_1") (pintype "passive"))
      (node (ref "R31") (pin "2") (pinfunction "2_2") (pintype "passive"))
    )
    (net (code "36") (name "Net-(IC3-C)") (class "Default")
      (node (ref "C23") (pin "1") (pinfunction "1_1") (pintype "passive"))
      (node (ref "IC3") (pin "1") (pinfunction "C_1") (pintype "passive"))
      (node (ref "OK3") (pin "2") (pinfunction "C_2") (pintype "passive"))
      (node (ref "R28") (pin "2") (pinfunction "2_2") (pintype "passive"))
    )
    (net (code "37") (name "Net-(IC3-REF)") (class "Default")
      (node (ref "C20") (pin "2") (pinfunction "2_2") (pintype "passive"))
      (node (ref "IC3") (pin "2") (pinfunction "REF_2") (pintype "passive"))
      (node (ref "R27") (pin "1") (pinfunction "1_1") (pintype "passive"))
      (node (ref "R30") (pin "2") (pinfunction "2_2") (pintype "passive"))
      (node (ref "R34") (pin "2") (pinfunction "2_2") (pintype "passive"))
    )
    (net (code "38") (name "Net-(JP2-PadCOM)") (class "Default")
      (node (ref "JP2") (pin "COM") (pinfunction "COM_COM") (pintype "passive"))
      (node (ref "R25") (pin "1") (pinfunction "1_1") (pintype "passive"))
    )
    (net (code "39") (name "Net-(L2-1)") (class "Default")
      (node (ref "B1") (pin "+") (pinfunction "+_+") (pintype "passive"))
      (node (ref "C8") (pin "+") (pinfunction "+_+") (pintype "passive"))
      (node (ref "L2") (pin "P$1") (pinfunction "1_P$1") (pintype "passive"))
    )
    (net (code "40") (name "Net-(LED1-PadC)") (class "Default")
      (node (ref "LED1") (pin "C") (pinfunction "C_C") (pintype "passive"))
      (node (ref "R13") (pin "1") (pinfunction "1_1") (pintype "passive"))
    )
    (net (code "41") (name "Net-(LED2-PadC)") (class "Default")
      (node (ref "LED2") (pin "C") (pinfunction "C_C") (pintype "passive"))
      (node (ref "R24") (pin "1") (pinfunction "1_1") (pintype "passive"))
    )
    (net (code "42") (name "Net-(NTC1-P$2)") (class "Default")
      (node (ref "NTC1") (pin "2") (pinfunction "P$2_2") (pintype "bidirectional"))
      (node (ref "Q1") (pin "A1") (pinfunction "A1_A1") (pintype "passive"))
      (node (ref "R1") (pin "1") (pinfunction "1_1") (pintype "passive"))
    )
    (net (code "43") (name "Net-(OK1-A1)") (class "Default")
      (node (ref "OK1") (pin "4") (pinfunction "A1_4") (pintype "passive"))
      (node (ref "R5") (pin "1") (pinfunction "1_1") (pintype "passive"))
    )
    (net (code "44") (name "Net-(OK1-A2)") (class "Default")
      (node (ref "OK1") (pin "6") (pinfunction "A2_6") (pintype "passive"))
      (node (ref "Q2") (pin "G") (pinfunction "G_G") (pintype "passive"))
      (node (ref "R4") (pin "1") (pinfunction "1_1") (pintype "passive"))
    )
    (net (code "45") (name "Net-(OK1-C)") (class "Default")
      (node (ref "OK1") (pin "2") (pinfunction "C_2") (pintype "passive"))
      (node (ref "R2") (pin "1") (pinfunction "1_1") (pintype "passive"))
    )
    (net (code "46") (name "Net-(OK2-A1)") (class "Default")
      (node (ref "OK2") (pin "4") (pinfunction "A1_4") (pintype "passive"))
      (node (ref "Q1") (pin "G") (pinfunction "G_G") (pintype "passive"))
      (node (ref "R1") (pin "2") (pinfunction "2_2") (pintype "passive"))
    )
    (net (code "47") (name "Net-(OK2-A2)") (class "Default")
      (node (ref "OK2") (pin "6") (pinfunction "A2_6") (pintype "passive"))
      (node (ref "R8") (pin "1") (pinfunction "1_1") (pintype "passive"))
    )
    (net (code "48") (name "Net-(OK2-C)") (class "Default")
      (node (ref "OK2") (pin "2") (pinfunction "C_2") (pintype "passive"))
      (node (ref "R6") (pin "1") (pinfunction "1_1") (pintype "passive"))
    )
    (net (code "49") (name "Net-(OK3-A)") (class "Default")
      (node (ref "OK3") (pin "1") (pinfunction "A_1") (pintype "passive"))
      (node (ref "R25") (pin "2") (pinfunction "2_2") (pintype "passive"))
      (node (ref "R28") (pin "1") (pinfunction "1_1") (pintype "passive"))
    )
    (net (code "50") (name "Net-(Q4-D)") (class "Default")
      (node (ref "Q4") (pin "3") (pinfunction "D_3") (pintype "passive"))
      (node (ref "R7") (pin "2") (pinfunction "2_2") (pintype "passive"))
    )
    (net (code "51") (name "Net-(Q6-D)") (class "Default")
      (node (ref "Q6") (pin "3") (pinfunction "D_3") (pintype "passive"))
      (node (ref "R13") (pin "2") (pinfunction "2_2") (pintype "passive"))
    )
    (net (code "52") (name "Net-(R2-Pad2)") (class "Default")
      (node (ref "R2") (pin "2") (pinfunction "2_2") (pintype "passive"))
      (node (ref "R3") (pin "1") (pinfunction "1_1") (pintype "passive"))
    )
    (net (code "53") (name "Net-(R6-Pad2)") (class "Default")
      (node (ref "R6") (pin "2") (pinfunction "2_2") (pintype "passive"))
      (node (ref "R7") (pin "1") (pinfunction "1_1") (pintype "passive"))
    )
    (net (code "54") (name "Net-(R18-Pad2)") (class "Default")
      (node (ref "R18") (pin "2") (pinfunction "2_2") (pintype "passive"))
      (node (ref "R20") (pin "1") (pinfunction "1_1") (pintype "passive"))
    )
    (net (code "55") (name "Net-(VAR1-P$1)") (class "Default")
      (node (ref "SAR1") (pin "P$1") (pinfunction "P$1_P$1") (pintype "bidirectional"))
      (node (ref "VAR1") (pin "1") (pinfunction "P$1_1") (pintype "bidirectional"))
      (node (ref "VAR2") (pin "2") (pinfunction "P$2_2") (pintype "bidirectional"))
    )
    (net (code "56") (name "Net-(X4A-S)") (class "Default")
      (node (ref "C3") (pin "1") (pinfunction "1_1") (pintype "passive"))
      (node (ref "C4") (pin "1") (pinfunction "1_1") (pintype "passive"))
      (node (ref "D1") (pin "C") (pinfunction "C_C") (pintype "passive"))
      (node (ref "L1") (pin "1") (pinfunction "1_1") (pintype "passive"))
      (node (ref "R12") (pin "2") (pinfunction "2_2") (pintype "passive"))
      (node (ref "X4") (pin "1") (pinfunction "S_1") (pintype "passive"))
    )
    (net (code "57") (name "Net-(X4B-S)") (class "Default")
      (node (ref "D1") (pin "A") (pinfunction "A_A") (pintype "passive"))
      (node (ref "Q5") (pin "2") (pinfunction "D_2") (pintype "passive"))
      (node (ref "Q5") (pin "4") (pinfunction "D_4") (pintype "passive"))
      (node (ref "X4") (pin "2") (pinfunction "S_2") (pintype "passive"))
    )
    (net (code "58") (name "Net-(X4C-S)") (class "Default")
      (node (ref "R12") (pin "1") (pinfunction "1_1") (pintype "passive"))
      (node (ref "R15") (pin "2") (pinfunction "2_2") (pintype "passive"))
      (node (ref "X4") (pin "3") (pinfunction "S_3") (pintype "passive"))
    )
    (net (code "59") (name "PE") (class "Default")
      (node (ref "J1") (pin "PE") (pinfunction "PE_PE") (pintype "bidirectional"))
      (node (ref "J2") (pin "P$1") (pinfunction "P$1_P$1") (pintype "bidirectional"))
      (node (ref "J2") (pin "P$2") (pinfunction "P$1_P$2") (pintype "bidirectional"))
      (node (ref "J3") (pin "P$1") (pinfunction "P$1_P$1") (pintype "bidirectional"))
      (node (ref "J3") (pin "P$2") (pinfunction "P$1_P$2") (pintype "bidirectional"))
      (node (ref "J4") (pin "P$1") (pinfunction "P$1_P$1") (pintype "bidirectional"))
      (node (ref "J4") (pin "P$2") (pinfunction "P$1_P$2") (pintype "bidirectional"))
      (node (ref "J5") (pin "1") (pinfunction "1_1") (pintype "passive"))
      (node (ref "J5") (pin "NC1") (pinfunction "1_NC1") (pintype "passive"))
      (node (ref "J5") (pin "NC2") (pinfunction "1_NC2") (pintype "passive"))
      (node (ref "J5") (pin "NC3") (pinfunction "1_NC3") (pintype "passive"))
      (node (ref "J5") (pin "NC4") (pinfunction "1_NC4") (pintype "passive"))
      (node (ref "JP1") (pin "NC") (pinfunction "NC_NC") (pintype "passive"))
      (node (ref "SAR1") (pin "P$2") (pinfunction "P$2_P$2") (pintype "bidirectional"))
      (node (ref "SW1") (pin "PE1") (pinfunction "PE_PE1") (pintype "power_in"))
      (node (ref "SW1") (pin "PE2") (pinfunction "PE_PE2") (pintype "power_in"))
      (node (ref "X1") (pin "3") (pinfunction "1_3") (pintype "passive"))
      (node (ref "X1") (pin "6") (pinfunction "1_6") (pintype "passive"))
      (node (ref "X2") (pin "3") (pinfunction "1_3") (pintype "passive"))
      (node (ref "X3") (pin "1") (pinfunction "1_1") (pintype "passive"))
      (node (ref "X3") (pin "2") (pinfunction "1_2") (pintype "passive"))
      (node (ref "ZD1") (pin "C") (pinfunction "1_C") (pintype "passive"))
      (node (ref "ZD2") (pin "C") (pinfunction "1_C") (pintype "passive"))
    )
    (net (code "60") (name "PWR_DIRECT") (class "Default")
      (node (ref "Q3") (pin "1") (pinfunction "G_1") (pintype "passive"))
      (node (ref "X3") (pin "12") (pinfunction "1_12") (pintype "passive"))
    )
    (net (code "61") (name "PWR_DIR_OUT") (class "Default")
      (node (ref "Q3") (pin "3") (pinfunction "D_3") (pintype "passive"))
      (node (ref "Q6") (pin "1") (pinfunction "G_1") (pintype "passive"))
      (node (ref "R14") (pin "2") (pinfunction "2_2") (pintype "passive"))
      (node (ref "R3") (pin "2") (pinfunction "2_2") (pintype "passive"))
    )
    (net (code "62") (name "PWR_SSTART") (class "Default")
      (node (ref "Q4") (pin "1") (pinfunction "G_1") (pintype "passive"))
      (node (ref "X3") (pin "11") (pinfunction "1_11") (pintype "passive"))
    )
    (net (code "63") (name "TEMP1_N") (class "Default")
      (node (ref "IC1") (pin "9") (pinfunction "IN-_9") (pintype "input"))
      (node (ref "X5") (pin "2") (pinfunction "S_2") (pintype "passive"))
    )
    (net (code "64") (name "TEMP1_P") (class "Default")
      (node (ref "IC1") (pin "10") (pinfunction "IN+_10") (pintype "input"))
      (node (ref "X5") (pin "1") (pinfunction "S_1") (pintype "passive"))
    )
    (net (code "65") (name "VIPER_D") (class "Default")
      (node (ref "D3") (pin "A") (pinfunction "A_A") (pintype "passive"))
      (node (ref "IC2") (pin "13") (pinfunction "DRAIN_13") (pintype "output"))
      (node (ref "IC2") (pin "14") (pinfunction "DRAIN_14") (pintype "output"))
      (node (ref "IC2") (pin "15") (pinfunction "DRAIN_15") (pintype "output"))
      (node (ref "IC2") (pin "16") (pinfunction "DRAIN_16") (pintype "output"))
      (node (ref "TP1") (pin "1") (pinfunction "P$1_1") (pintype "bidirectional"))
      (node (ref "TR1") (pin "4") (pinfunction "P1_DOT_4") (pintype "passive"))
      (node (ref "TR1B") (pin "9") (pinfunction "P1_DOT_9") (pintype "passive"))
    )
    (net (code "66") (name "unconnected-(IC1-~{OVR}-Pad3)") (class "Default")
      (node (ref "IC1") (pin "3") (pinfunction "~{OVR}_3") (pintype "output"))
    )
    (net (code "67") (name "unconnected-(IC1-~{SMBALERT}-Pad14)") (class "Default")
      (node (ref "IC1") (pin "14") (pinfunction "~{SMBALERT}_14") (pintype "output"))
    )
    (net (code "68") (name "unconnected-(IC1-~{THERM}-Pad7)") (class "Default")
      (node (ref "IC1") (pin "7") (pinfunction "~{THERM}_7") (pintype "bidirectional"))
    )
    (net (code "69") (name "unconnected-(KK1-K-PadA2,5)") (class "Default")
      (node (ref "KK1") (pin "A2,5") (pinfunction "K_A2,5") (pintype "passive"))
    )
    (net (code "70") (name "unconnected-(KK1-K-PadB2,5)") (class "Default")
      (node (ref "KK1") (pin "B2,5") (pinfunction "K_B2,5") (pintype "passive"))
    )
    (net (code "71") (name "unconnected-(TR1-P1_MIDDLE-Pad3)") (class "Default")
      (node (ref "TR1") (pin "3") (pinfunction "P1_MIDDLE_3") (pintype "passive"))
    )
  )
)
